# RF.net
KiCad netlist of a schematic drawn in Altium Designer
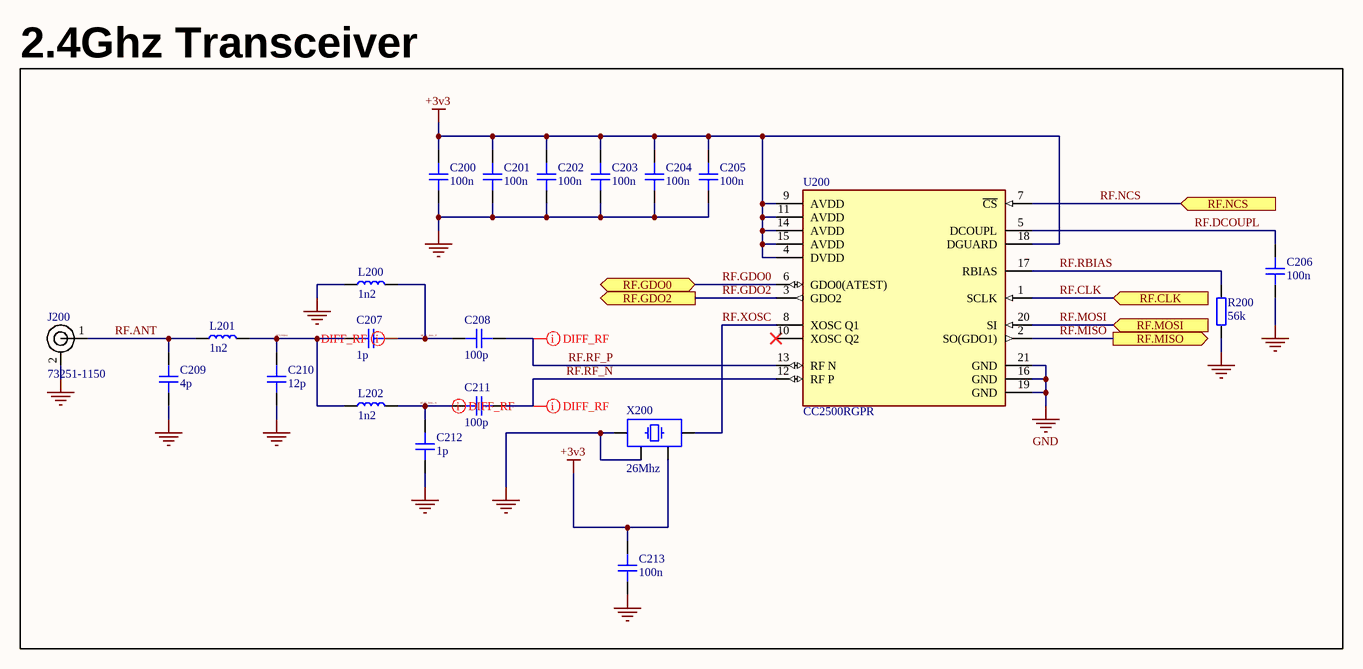
[diagram p0: RF.SchDoc]

(export (version "E")
  (design (tool "Eeschema 10.0.6"))
  (components
    (comp (ref "C200")
      (value "100n")
      (footprint "CAP_0402")
      (description "Capacitor SMD 0402 X7R 50V 10% 100nF")
      (libsource (lib "Schematic-Lib-PhilsLab") (part "CAP_0402"))
    )
    (comp (ref "C201")
      (value "100n")
      (footprint "CAP_0402")
      (description "Capacitor SMD 0402 X7R 50V 10% 100nF")
      (libsource (lib "Schematic-Lib-PhilsLab") (part "CAP_0402"))
    )
    (comp (ref "C202")
      (value "100n")
      (footprint "CAP_0402")
      (description "Capacitor SMD 0402 X7R 50V 10% 100nF")
      (libsource (lib "Schematic-Lib-PhilsLab") (part "CAP_0402"))
    )
    (comp (ref "C203")
      (value "100n")
      (footprint "CAP_0402")
      (description "Capacitor SMD 0402 X7R 50V 10% 100nF")
      (libsource (lib "Schematic-Lib-PhilsLab") (part "CAP_0402"))
    )
    (comp (ref "C204")
      (value "100n")
      (footprint "CAP_0402")
      (description "Capacitor SMD 0402 X7R 50V 10% 100nF")
      (libsource (lib "Schematic-Lib-PhilsLab") (part "CAP_0402"))
    )
    (comp (ref "C205")
      (value "100n")
      (footprint "CAP_0402")
      (description "Capacitor SMD 0402 X7R 50V 10% 100nF")
      (libsource (lib "Schematic-Lib-PhilsLab") (part "CAP_0402"))
    )
    (comp (ref "C206")
      (value "100n")
      (footprint "CAP_0402")
      (description "Capacitor SMD 0402 X7R 50V 10% 100nF")
      (libsource (lib "Schematic-Lib-PhilsLab") (part "CAP_0402"))
    )
    (comp (ref "C207")
      (value "1p")
      (footprint "CAP_0402")
      (description "Capacitor SMD 0402 C0G 50V +-0.25pF 1pF")
      (libsource (lib "Schematic-Lib-PhilsLab") (part "CAP_0402"))
    )
    (comp (ref "C208")
      (value "100p")
      (footprint "CAP_0402")
      (description "Capacitor SMD 0402 C0G 100V 1% 100pF")
      (libsource (lib "Schematic-Lib-PhilsLab") (part "CAP_0402"))
    )
    (comp (ref "C209")
      (value "4p")
      (footprint "CAP_0402")
      (description "Capacitor SMD 0402 C0G 50V +-0.25pF 4pF")
      (libsource (lib "Schematic-Lib-PhilsLab") (part "CAP_0402"))
    )
    (comp (ref "C210")
      (value "12p")
      (footprint "CAP_0402")
      (description "Capacitor SMD 0402 C0G 50V 2% 12pF")
      (libsource (lib "Schematic-Lib-PhilsLab") (part "CAP_0402"))
    )
    (comp (ref "C211")
      (value "100p")
      (footprint "CAP_0402")
      (description "Capacitor SMD 0402 C0G 100V 1% 100pFCapacitor SMD 0402 C0G 100V 1% 100pF")
      (libsource (lib "Schematic-Lib-PhilsLab") (part "CAP_0402"))
    )
    (comp (ref "C212")
      (value "1p")
      (footprint "CAP_0402")
      (description "Capacitor SMD 0402 C0G 50V +-0.25pF 1pF")
      (libsource (lib "Schematic-Lib-PhilsLab") (part "CAP_0402"))
    )
    (comp (ref "C213")
      (value "100n")
      (footprint "CAP_0402")
      (description "Capacitor SMD 0402 X7R 50V 10% 100nF")
      (libsource (lib "Schematic-Lib-PhilsLab") (part "CAP_0402"))
    )
    (comp (ref "J200")
      (value "73251-1150")
      (footprint "73251-1150")
      (description "RF Connector 50 Ohms, SMA Jack Receptacle, Edge Mount, .25µm Gold (Au) Plating")
      (fields (field (name "MANUFACTURER") "Molex"))
      (libsource (lib "Schematic-Lib-PhilsLab") (part "73251-1150"))
    )
    (comp (ref "L200")
      (value "1n2")
      (footprint "IND_0402")
      (description "Inductor SMD 0402 RF Unshielded 1.2nH 1A 70mΩ +-0.3nH")
      (libsource (lib "Schematic-Lib-PhilsLab") (part "IND_0402"))
    )
    (comp (ref "L201")
      (value "1n2")
      (footprint "IND_0402")
      (description "Inductor SMD 0402 RF Unshielded 1.2nH 1A 70mΩ +-0.3nH")
      (libsource (lib "Schematic-Lib-PhilsLab") (part "IND_0402"))
    )
    (comp (ref "L202")
      (value "1n2")
      (footprint "IND_0402")
      (description "Inductor SMD 0402 RF Unshielded 1.2nH 1A 70mΩ +-0.3nH")
      (libsource (lib "Schematic-Lib-PhilsLab") (part "IND_0402"))
    )
    (comp (ref "R200")
      (value "56k")
      (footprint "RES_0402")
      (description "Resistor SMD Thick Film 0402 75V 100mW 1% 56kΩ")
      (libsource (lib "Schematic-Lib-PhilsLab") (part "RES_0402"))
    )
    (comp (ref "U200")
      (value "CC2500RGPR")
      (footprint "FP-RGP0020C-MFG")
      (description "IC RF TXRX ISM>1GHZ 20VFQFN")
      (libsource (lib "Altium Content Vault") (part "2db98f27c02c3b1ee188219db266f3d"))
    )
    (comp (ref "X200")
      (value "26Mhz")
      (footprint "XTAL_2520")
      (description "Crystal SMD 2520")
      (fields (field (name "MANUFACTURER PART NUMBER") "OW3EL89CENUNFAYLC-26M"))
      (libsource (lib "Schematic-Lib-PhilsLab") (part "XTAL_2520"))
    )
  )
  (nets
    (net (code "1") (name "+3v3") (class "Default")
      (node (ref "C200") (pin "1") (pinfunction "1_1") (pintype "passive"))
      (node (ref "C201") (pin "1") (pinfunction "1_1") (pintype "passive"))
      (node (ref "C202") (pin "1") (pinfunction "1_1") (pintype "passive"))
      (node (ref "C203") (pin "1") (pinfunction "1_1") (pintype "passive"))
      (node (ref "C204") (pin "1") (pinfunction "1_1") (pintype "passive"))
      (node (ref "C205") (pin "1") (pinfunction "1_1") (pintype "passive"))
      (node (ref "C213") (pin "1") (pinfunction "1_1") (pintype "passive"))
      (node (ref "U200") (pin "11") (pinfunction "AVDD_11") (pintype "power_in"))
      (node (ref "U200") (pin "14") (pinfunction "AVDD_14") (pintype "power_in"))
      (node (ref "U200") (pin "15") (pinfunction "AVDD_15") (pintype "power_in"))
      (node (ref "U200") (pin "18") (pinfunction "DGUARD_18") (pintype "power_in"))
      (node (ref "U200") (pin "4") (pinfunction "DVDD_4") (pintype "power_in"))
      (node (ref "U200") (pin "9") (pinfunction "AVDD_9") (pintype "power_in"))
      (node (ref "X200") (pin "2") (pinfunction "2_2") (pintype "passive"))
    )
    (net (code "2") (name "/RF.ANT") (class "Default")
      (node (ref "C209") (pin "1") (pinfunction "1_1") (pintype "passive"))
      (node (ref "J200") (pin "1") (pinfunction "1_1") (pintype "passive"))
      (node (ref "L201") (pin "2") (pinfunction "2_2") (pintype "passive"))
    )
    (net (code "3") (name "/RF.CLK") (class "Default")
      (node (ref "U200") (pin "1") (pinfunction "SCLK_1") (pintype "input"))
    )
    (net (code "4") (name "/RF.DCOUPL") (class "Default")
      (node (ref "C206") (pin "1") (pinfunction "1_1") (pintype "passive"))
      (node (ref "U200") (pin "5") (pinfunction "DCOUPL_5") (pintype "power_in"))
    )
    (net (code "5") (name "/RF.GDO0") (class "Default")
      (node (ref "U200") (pin "6") (pinfunction "GDO0(ATEST)_6") (pintype "bidirectional"))
    )
    (net (code "6") (name "/RF.GDO2") (class "Default")
      (node (ref "U200") (pin "3") (pinfunction "GDO2_3") (pintype "output"))
    )
    (net (code "7") (name "/RF.MISO") (class "Default")
      (node (ref "U200") (pin "2") (pinfunction "SO(GDO1)_2") (pintype "output"))
    )
    (net (code "8") (name "/RF.MOSI") (class "Default")
      (node (ref "U200") (pin "20") (pinfunction "SI_20") (pintype "input"))
    )
    (net (code "9") (name "/RF.NCS") (class "Default")
      (node (ref "U200") (pin "7") (pinfunction "~{CS}_7") (pintype "input"))
    )
    (net (code "10") (name "/RF.RBIAS") (class "Default")
      (node (ref "R200") (pin "2") (pinfunction "2_2") (pintype "passive"))
      (node (ref "U200") (pin "17") (pinfunction "RBIAS_17") (pintype "passive"))
    )
    (net (code "11") (name "/RF.RF_BAL_N") (class "Default")
      (node (ref "C211") (pin "1") (pinfunction "1_1") (pintype "passive"))
      (node (ref "C212") (pin "1") (pinfunction "1_1") (pintype "passive"))
      (node (ref "L202") (pin "1") (pinfunction "1_1") (pintype "passive"))
    )
    (net (code "12") (name "/RF.RF_BAL_P") (class "Default")
      (node (ref "C207") (pin "2") (pinfunction "2_2") (pintype "passive"))
      (node (ref "C208") (pin "1") (pinfunction "1_1") (pintype "passive"))
      (node (ref "L200") (pin "1") (pinfunction "1_1") (pintype "passive"))
    )
    (net (code "13") (name "/RF.RF_N") (class "Default")
      (node (ref "C211") (pin "2") (pinfunction "2_2") (pintype "passive"))
      (node (ref "U200") (pin "12") (pinfunction "RF_P_12") (pintype "bidirectional"))
    )
    (net (code "14") (name "/RF.RF_P") (class "Default")
      (node (ref "C208") (pin "2") (pinfunction "2_2") (pintype "passive"))
      (node (ref "U200") (pin "13") (pinfunction "RF_N_13") (pintype "bidirectional"))
    )
    (net (code "15") (name "/RF.UNBAL") (class "Default")
      (node (ref "C207") (pin "1") (pinfunction "1_1") (pintype "passive"))
      (node (ref "C210") (pin "1") (pinfunction "1_1") (pintype "passive"))
      (node (ref "L201") (pin "1") (pinfunction "1_1") (pintype "passive"))
      (node (ref "L202") (pin "2") (pinfunction "2_2") (pintype "passive"))
    )
    (net (code "16") (name "/RF.XOSC") (class "Default")
      (node (ref "U200") (pin "8") (pinfunction "XOSC_Q1_8") (pintype "passive"))
      (node (ref "X200") (pin "1") (pinfunction "1_1") (pintype "passive"))
    )
    (net (code "17") (name "GND") (class "Default")
      (node (ref "C200") (pin "2") (pinfunction "2_2") (pintype "passive"))
      (node (ref "C201") (pin "2") (pinfunction "2_2") (pintype "passive"))
      (node (ref "C202") (pin "2") (pinfunction "2_2") (pintype "passive"))
      (node (ref "C203") (pin "2") (pinfunction "2_2") (pintype "passive"))
      (node (ref "C204") (pin "2") (pinfunction "2_2") (pintype "passive"))
      (node (ref "C205") (pin "2") (pinfunction "2_2") (pintype "passive"))
      (node (ref "C206") (pin "2") (pinfunction "2_2") (pintype "passive"))
      (node (ref "C209") (pin "2") (pinfunction "2_2") (pintype "passive"))
      (node (ref "C210") (pin "2") (pinfunction "2_2") (pintype "passive"))
      (node (ref "C212") (pin "2") (pinfunction "2_2") (pintype "passive"))
      (node (ref "C213") (pin "2") (pinfunction "2_2") (pintype "passive"))
      (node (ref "J200") (pin "2") (pinfunction "2_2") (pintype "passive"))
      (node (ref "L200") (pin "2") (pinfunction "2_2") (pintype "passive"))
      (node (ref "R200") (pin "1") (pinfunction "1_1") (pintype "passive"))
      (node (ref "U200") (pin "16") (pinfunction "GND_16") (pintype "power_in"))
      (node (ref "U200") (pin "19") (pinfunction "GND_19") (pintype "power_in"))
      (node (ref "U200") (pin "21") (pinfunction "GND_21") (pintype "power_in"))
      (node (ref "X200") (pin "3") (pinfunction "3_3") (pintype "passive"))
      (node (ref "X200") (pin "4") (pinfunction "4_4") (pintype "passive"))
    )
    (net (code "18") (name "unconnected-(U200-XOSC_Q2-Pad10)") (class "Default")
      (node (ref "U200") (pin "10") (pinfunction "XOSC_Q2_10") (pintype "passive+no_connect"))
    )
  )
)
